# OLED-CAM-M8.net
KiCad netlist of a schematic drawn in EAGLE
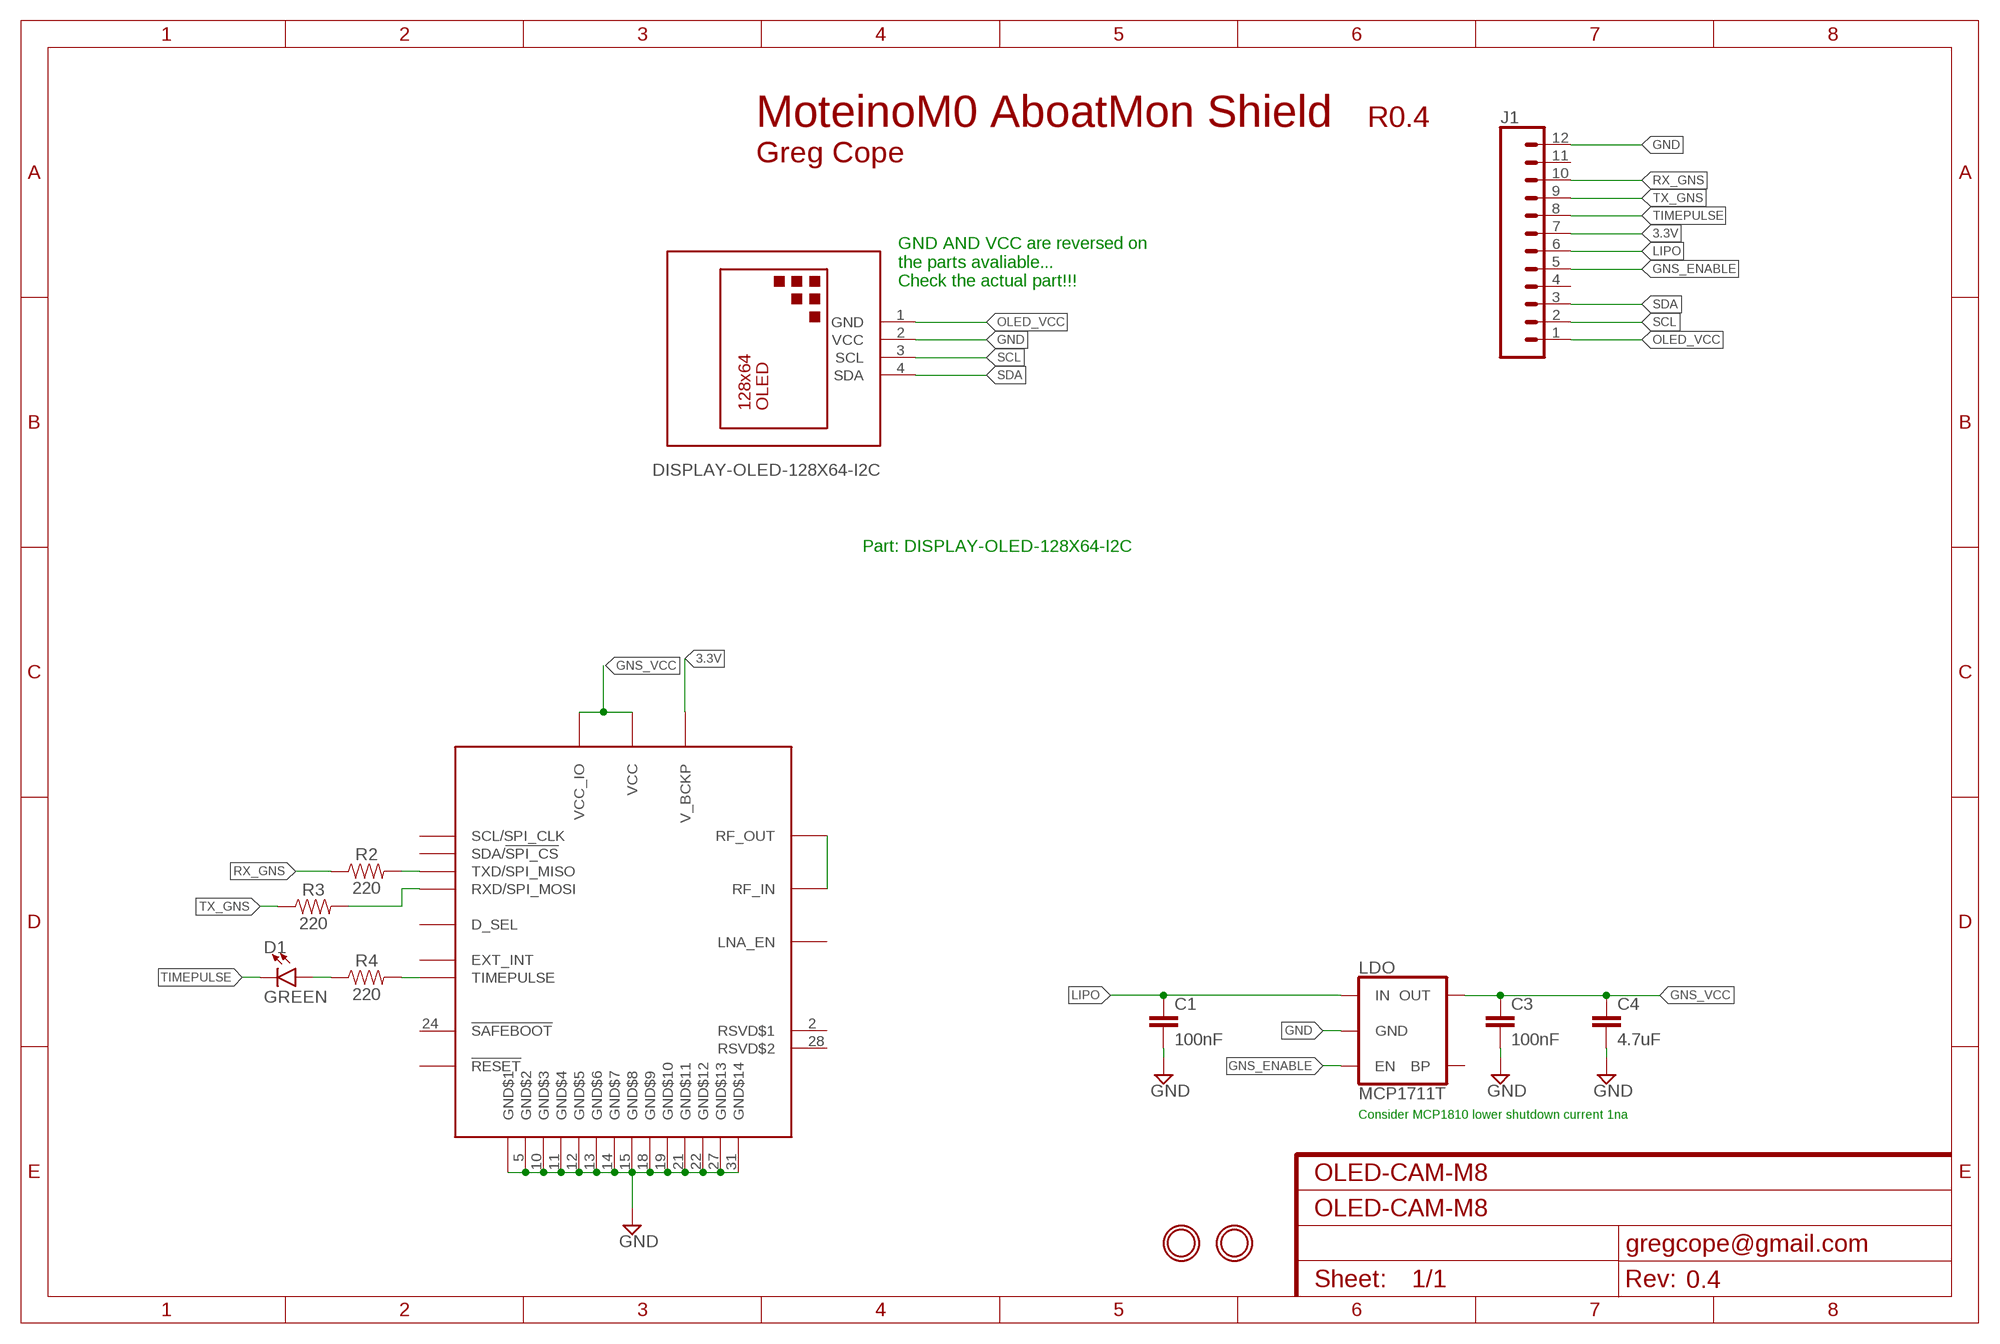
[diagram p0: schematic, sheet 1]

(export (version "E")
  (design (tool "Eeschema 10.0.6"))
  (components
    (comp (ref "C1")
      (value "100nF")
      (footprint "eagle-import:0603")
      (libsource (lib "eagle-import") (part "0.1UF-0603-25V-5%"))
    )
    (comp (ref "C3")
      (value "100nF")
      (footprint "eagle-import:0603")
      (libsource (lib "eagle-import") (part "0.1UF-0603-25V-5%"))
    )
    (comp (ref "C4")
      (value "4.7uF")
      (footprint "eagle-import:0603")
      (libsource (lib "eagle-import") (part "4.7UF0603"))
    )
    (comp (ref "D1")
      (value "GREEN")
      (footprint "eagle-import:LED-0603")
      (libsource (lib "eagle-import") (part "LED-GREEN0603"))
    )
    (comp (ref "GND")
      (value "MOUNTINGHOLE2.5")
      (footprint "eagle-import:MOUNTINGHOLE_2.5_PLATED")
      (libsource (lib "eagle-import") (part "MOUNTINGHOLE2.5"))
    )
    (comp (ref "J1")
      (value "CONN_12")
      (footprint "eagle-import:1X12")
      (libsource (lib "eagle-import") (part "CONN_12"))
    )
    (comp (ref "LDO")
      (value "MCP1711T")
      (footprint "eagle-import:SOT23-5")
      (libsource (lib "eagle-import") (part "V_REG_SPX3819-SOT23-5"))
    )
    (comp (ref "R2")
      (value "220")
      (footprint "eagle-import:0603")
      (libsource (lib "eagle-import") (part "220OHM-0603-1/10W-1%"))
    )
    (comp (ref "R3")
      (value "220")
      (footprint "eagle-import:0603")
      (libsource (lib "eagle-import") (part "220OHM-0603-1/10W-1%"))
    )
    (comp (ref "R4")
      (value "220")
      (footprint "eagle-import:0603")
      (libsource (lib "eagle-import") (part "220OHM-0603-1/10W-1%"))
    )
    (comp (ref "U$2")
      (value "DISPLAY-OLED-128X64-I2C")
      (footprint "eagle-import:DISPLAY-OLED-128X64-I2C")
      (libsource (lib "eagle-import") (part "DISPLAY-OLED-128X64-I2C"))
    )
    (comp (ref "U$5")
      (value "CAM-M8")
      (footprint "eagle-import:CAM-M8")
      (libsource (lib "eagle-import") (part "CAM-M8"))
    )
    (comp (ref "U$7")
      (value "MOUNTINGHOLE2.5")
      (footprint "eagle-import:MOUNTINGHOLE_2.5_PLATED")
      (libsource (lib "eagle-import") (part "MOUNTINGHOLE2.5"))
    )
  )
  (nets
    (net (code "1") (name "3.3V") (class "Default")
      (node (ref "J1") (pin "7") (pinfunction "7_7") (pintype "passive"))
      (node (ref "U$5") (pin "8") (pinfunction "V_BCKP_8") (pintype "power_in"))
    )
    (net (code "2") (name "GND") (class "Default")
      (node (ref "C1") (pin "2") (pinfunction "2_2") (pintype "passive"))
      (node (ref "C3") (pin "2") (pinfunction "2_2") (pintype "passive"))
      (node (ref "C4") (pin "2") (pinfunction "2_2") (pintype "passive"))
      (node (ref "J1") (pin "12") (pinfunction "12_12") (pintype "passive"))
      (node (ref "LDO") (pin "2") (pinfunction "GND_2") (pintype "input"))
      (node (ref "U$2") (pin "2") (pinfunction "VCC_2") (pintype "power_in"))
      (node (ref "U$5") (pin "10") (pinfunction "GND$3_10") (pintype "power_in"))
      (node (ref "U$5") (pin "11") (pinfunction "GND$4_11") (pintype "power_in"))
      (node (ref "U$5") (pin "12") (pinfunction "GND$5_12") (pintype "power_in"))
      (node (ref "U$5") (pin "13") (pinfunction "GND$6_13") (pintype "power_in"))
      (node (ref "U$5") (pin "14") (pinfunction "GND$7_14") (pintype "power_in"))
      (node (ref "U$5") (pin "15") (pinfunction "GND$8_15") (pintype "power_in"))
      (node (ref "U$5") (pin "18") (pinfunction "GND$9_18") (pintype "power_in"))
      (node (ref "U$5") (pin "19") (pinfunction "GND$10_19") (pintype "power_in"))
      (node (ref "U$5") (pin "21") (pinfunction "GND$11_21") (pintype "power_in"))
      (node (ref "U$5") (pin "22") (pinfunction "GND$12_22") (pintype "power_in"))
      (node (ref "U$5") (pin "27") (pinfunction "GND$13_27") (pintype "power_in"))
      (node (ref "U$5") (pin "31") (pinfunction "GND$14_31") (pintype "power_in"))
      (node (ref "U$5") (pin "4") (pinfunction "GND$1_4") (pintype "power_in"))
      (node (ref "U$5") (pin "5") (pinfunction "GND$2_5") (pintype "power_in"))
    )
    (net (code "3") (name "GNS_ENABLE") (class "Default")
      (node (ref "J1") (pin "5") (pinfunction "5_5") (pintype "passive"))
      (node (ref "LDO") (pin "3") (pinfunction "EN_3") (pintype "input"))
    )
    (net (code "4") (name "GNS_VCC") (class "Default")
      (node (ref "C3") (pin "1") (pinfunction "1_1") (pintype "passive"))
      (node (ref "C4") (pin "1") (pinfunction "1_1") (pintype "passive"))
      (node (ref "LDO") (pin "5") (pinfunction "OUT_5") (pintype "passive"))
      (node (ref "U$5") (pin "1") (pinfunction "VCC_IO_1") (pintype "power_in"))
      (node (ref "U$5") (pin "9") (pinfunction "VCC_9") (pintype "power_in"))
    )
    (net (code "5") (name "LIPO") (class "Default")
      (node (ref "C1") (pin "1") (pinfunction "1_1") (pintype "passive"))
      (node (ref "J1") (pin "6") (pinfunction "6_6") (pintype "passive"))
      (node (ref "LDO") (pin "1") (pinfunction "IN_1") (pintype "input"))
    )
    (net (code "6") (name "Net-(D1-PadA)") (class "Default")
      (node (ref "D1") (pin "A") (pinfunction "A_A") (pintype "passive"))
      (node (ref "R4") (pin "1") (pinfunction "1_1") (pintype "passive"))
    )
    (net (code "7") (name "Net-(U$5-RF_IN)") (class "Default")
      (node (ref "U$5") (pin "16") (pinfunction "RF_OUT_16") (pintype "output"))
      (node (ref "U$5") (pin "17") (pinfunction "RF_IN_17") (pintype "input"))
    )
    (net (code "8") (name "Net-(U$5-RXD{slash}SPI_MOSI)") (class "Default")
      (node (ref "R3") (pin "2") (pinfunction "2_2") (pintype "passive"))
      (node (ref "U$5") (pin "26") (pinfunction "RXD/SPI_MOSI_26") (pintype "input"))
    )
    (net (code "9") (name "Net-(U$5-TIMEPULSE)") (class "Default")
      (node (ref "R4") (pin "2") (pinfunction "2_2") (pintype "passive"))
      (node (ref "U$5") (pin "29") (pinfunction "TIMEPULSE_29") (pintype "output"))
    )
    (net (code "10") (name "Net-(U$5-TXD{slash}SPI_MISO)") (class "Default")
      (node (ref "R2") (pin "2") (pinfunction "2_2") (pintype "passive"))
      (node (ref "U$5") (pin "25") (pinfunction "TXD/SPI_MISO_25") (pintype "output"))
    )
    (net (code "11") (name "OLED_VCC") (class "Default")
      (node (ref "J1") (pin "1") (pinfunction "1_1") (pintype "passive"))
      (node (ref "U$2") (pin "1") (pinfunction "GND_1") (pintype "power_in"))
    )
    (net (code "12") (name "RX_GNS") (class "Default")
      (node (ref "J1") (pin "10") (pinfunction "10_10") (pintype "passive"))
      (node (ref "R2") (pin "1") (pinfunction "1_1") (pintype "passive"))
    )
    (net (code "13") (name "SCL") (class "Default")
      (node (ref "J1") (pin "2") (pinfunction "2_2") (pintype "passive"))
      (node (ref "U$2") (pin "3") (pinfunction "SCL_3") (pintype "bidirectional"))
    )
    (net (code "14") (name "SDA") (class "Default")
      (node (ref "J1") (pin "3") (pinfunction "3_3") (pintype "passive"))
      (node (ref "U$2") (pin "4") (pinfunction "SDA_4") (pintype "bidirectional"))
    )
    (net (code "15") (name "TIMEPULSE") (class "Default")
      (node (ref "D1") (pin "C") (pinfunction "C_C") (pintype "passive"))
      (node (ref "J1") (pin "8") (pinfunction "8_8") (pintype "passive"))
    )
    (net (code "16") (name "TX_GNS") (class "Default")
      (node (ref "J1") (pin "9") (pinfunction "9_9") (pintype "passive"))
      (node (ref "R3") (pin "1") (pinfunction "1_1") (pintype "passive"))
    )
    (net (code "17") (name "unconnected-(J1-Pad4)") (class "Default")
      (node (ref "J1") (pin "4") (pinfunction "4_4") (pintype "passive"))
    )
    (net (code "18") (name "unconnected-(J1-Pad11)") (class "Default")
      (node (ref "J1") (pin "11") (pinfunction "11_11") (pintype "passive"))
    )
    (net (code "19") (name "unconnected-(LDO-BP-Pad4)") (class "Default")
      (node (ref "LDO") (pin "4") (pinfunction "BP_4") (pintype "input"))
    )
    (net (code "20") (name "unconnected-(U$5-D_SEL-Pad20)") (class "Default")
      (node (ref "U$5") (pin "20") (pinfunction "D_SEL_20") (pintype "input"))
    )
    (net (code "21") (name "unconnected-(U$5-EXT_INT-Pad7)") (class "Default")
      (node (ref "U$5") (pin "7") (pinfunction "EXT_INT_7") (pintype "bidirectional"))
    )
    (net (code "22") (name "unconnected-(U$5-LNA_EN-Pad30)") (class "Default")
      (node (ref "U$5") (pin "30") (pinfunction "LNA_EN_30") (pintype "output"))
    )
    (net (code "23") (name "unconnected-(U$5-RSVD$1-Pad2)") (class "Default")
      (node (ref "U$5") (pin "2") (pinfunction "RSVD$1_2") (pintype "no_connect"))
    )
    (net (code "24") (name "unconnected-(U$5-RSVD$2-Pad28)") (class "Default")
      (node (ref "U$5") (pin "28") (pinfunction "RSVD$2_28") (pintype "no_connect"))
    )
    (net (code "25") (name "unconnected-(U$5-SCL{slash}SPI_CLK-Pad6)") (class "Default")
      (node (ref "U$5") (pin "6") (pinfunction "SCL/SPI_CLK_6") (pintype "input"))
    )
    (net (code "26") (name "unconnected-(U$5-SDA{slash}~{SPI_CS}-Pad3)") (class "Default")
      (node (ref "U$5") (pin "3") (pinfunction "SDA/~{SPI_CS}_3") (pintype "bidirectional"))
    )
    (net (code "27") (name "unconnected-(U$5-~{RESET}-Pad23)") (class "Default")
      (node (ref "U$5") (pin "23") (pinfunction "~{RESET}_23") (pintype "input"))
    )
    (net (code "28") (name "unconnected-(U$5-~{SAFEBOOT}-Pad24)") (class "Default")
      (node (ref "U$5") (pin "24") (pinfunction "~{SAFEBOOT}_24") (pintype "input"))
    )
  )
)
